# schemat.net
KiCad netlist of a schematic drawn in EAGLE
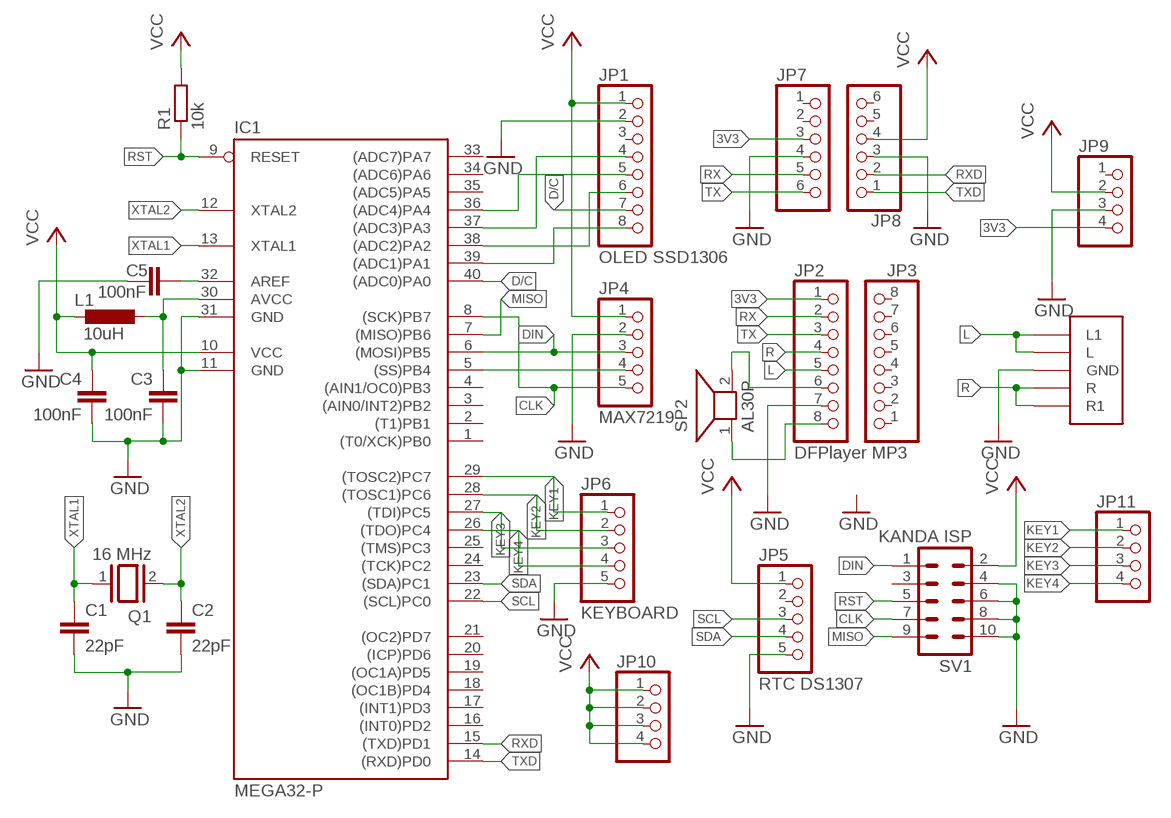
[diagram p0: schematic, sheet 1]

(export (version "E")
  (design (tool "Eeschema 10.0.6"))
  (components
    (comp (ref "C1")
      (value "22pF")
      (footprint "eagle-import:C025-025X050")
      (libsource (lib "eagle-import") (part "C-EU025-025X050"))
    )
    (comp (ref "C2")
      (value "22pF")
      (footprint "eagle-import:C025-025X050")
      (libsource (lib "eagle-import") (part "C-EU025-025X050"))
    )
    (comp (ref "C3")
      (value "100nF")
      (footprint "eagle-import:C025-025X050")
      (libsource (lib "eagle-import") (part "C-EU025-025X050"))
    )
    (comp (ref "C4")
      (value "100nF")
      (footprint "eagle-import:C025-025X050")
      (libsource (lib "eagle-import") (part "C-EU025-025X050"))
    )
    (comp (ref "C5")
      (value "100nF")
      (footprint "eagle-import:C025-025X050")
      (libsource (lib "eagle-import") (part "C-EU025-025X050"))
    )
    (comp (ref "IC1")
      (value "MEGA32-P")
      (footprint "eagle-import:DIL40")
      (fields (field (name "MPN") "ATMEGA16-16PU"))
      (libsource (lib "eagle-import") (part "MEGA16-P"))
    )
    (comp (ref "JP1")
      (value "OLED SSD1306")
      (footprint "eagle-import:1X08")
      (libsource (lib "eagle-import") (part "PINHD-1X8"))
    )
    (comp (ref "JP2")
      (value "DFPlayer MP3")
      (footprint "eagle-import:1X08")
      (libsource (lib "eagle-import") (part "PINHD-1X8"))
    )
    (comp (ref "JP3")
      (value "PINHD-1X8")
      (footprint "eagle-import:1X08")
      (libsource (lib "eagle-import") (part "PINHD-1X8"))
    )
    (comp (ref "JP4")
      (value "MAX7219")
      (footprint "eagle-import:1X05")
      (libsource (lib "eagle-import") (part "PINHD-1X5"))
    )
    (comp (ref "JP5")
      (value "RTC DS1307")
      (footprint "eagle-import:1X05")
      (libsource (lib "eagle-import") (part "PINHD-1X5"))
    )
    (comp (ref "JP6")
      (value "KEYBOARD")
      (footprint "eagle-import:1X05")
      (libsource (lib "eagle-import") (part "PINHD-1X5"))
    )
    (comp (ref "JP7")
      (value "PINHD-1X6")
      (footprint "eagle-import:1X06")
      (libsource (lib "eagle-import") (part "PINHD-1X6"))
    )
    (comp (ref "JP8")
      (value "PINHD-1X6")
      (footprint "eagle-import:1X06")
      (libsource (lib "eagle-import") (part "PINHD-1X6"))
    )
    (comp (ref "JP9")
      (value "PINHD-1X4")
      (footprint "eagle-import:1X04")
      (libsource (lib "eagle-import") (part "PINHD-1X4"))
    )
    (comp (ref "JP10")
      (value "PINHD-1X4")
      (footprint "eagle-import:1X04")
      (libsource (lib "eagle-import") (part "PINHD-1X4"))
    )
    (comp (ref "JP11")
      (value "PINHD-1X4")
      (footprint "eagle-import:1X04")
      (libsource (lib "eagle-import") (part "PINHD-1X4"))
    )
    (comp (ref "L1")
      (value "10uH")
      (footprint "eagle-import:0204_5")
      (libsource (lib "eagle-import") (part "L-EU0204/5"))
    )
    (comp (ref "Q1")
      (value "16 MHz")
      (footprint "eagle-import:QS")
      (libsource (lib "eagle-import") (part "XTAL/S"))
    )
    (comp (ref "R1")
      (value "10k")
      (footprint "eagle-import:0207_7")
      (libsource (lib "eagle-import") (part "R-EU_0207/7"))
    )
    (comp (ref "SP2")
      (value "AL30P")
      (footprint "eagle-import:AL30P")
      (libsource (lib "eagle-import") (part "AL30P"))
    )
    (comp (ref "SV1")
      (value "KANDA ISP")
      (footprint "eagle-import:ML10")
      (libsource (lib "eagle-import") (part "ML10"))
    )
    (comp (ref "U$1")
      (value "STEREO_D")
      (footprint "eagle-import:STEREO_P")
      (libsource (lib "eagle-import") (part "STEREO_D"))
    )
  )
  (nets
    (net (code "1") (name "3V3") (class "Default")
      (node (ref "JP2") (pin "1") (pinfunction "1_1") (pintype "passive"))
      (node (ref "JP7") (pin "3") (pinfunction "3_3") (pintype "passive"))
      (node (ref "JP9") (pin "4") (pinfunction "4_4") (pintype "passive"))
    )
    (net (code "2") (name "CLK") (class "Default")
      (node (ref "IC1") (pin "8") (pinfunction "(SCK)PB7_8") (pintype "bidirectional"))
      (node (ref "JP4") (pin "5") (pinfunction "5_5") (pintype "passive"))
      (node (ref "SV1") (pin "7") (pinfunction "7_7") (pintype "passive"))
    )
    (net (code "3") (name "DIN") (class "Default")
      (node (ref "IC1") (pin "6") (pinfunction "(MOSI)PB5_6") (pintype "bidirectional"))
      (node (ref "JP4") (pin "3") (pinfunction "3_3") (pintype "passive"))
      (node (ref "SV1") (pin "1") (pinfunction "1_1") (pintype "passive"))
    )
    (net (code "4") (name "D{slash}C") (class "Default")
      (node (ref "IC1") (pin "40") (pinfunction "(ADC0)PA0_40") (pintype "bidirectional"))
      (node (ref "JP1") (pin "7") (pinfunction "7_7") (pintype "passive"))
    )
    (net (code "5") (name "GND") (class "Default")
      (node (ref "C1") (pin "2") (pinfunction "2_2") (pintype "passive"))
      (node (ref "C2") (pin "2") (pinfunction "2_2") (pintype "passive"))
      (node (ref "C3") (pin "2") (pinfunction "2_2") (pintype "passive"))
      (node (ref "C4") (pin "2") (pinfunction "2_2") (pintype "passive"))
      (node (ref "C5") (pin "2") (pinfunction "2_2") (pintype "passive"))
      (node (ref "IC1") (pin "11") (pinfunction "GND_11") (pintype "power_in"))
      (node (ref "IC1") (pin "31") (pinfunction "GND_31") (pintype "power_in"))
      (node (ref "JP1") (pin "2") (pinfunction "2_2") (pintype "passive"))
      (node (ref "JP2") (pin "7") (pinfunction "7_7") (pintype "passive"))
      (node (ref "JP4") (pin "2") (pinfunction "2_2") (pintype "passive"))
      (node (ref "JP5") (pin "5") (pinfunction "5_5") (pintype "passive"))
      (node (ref "JP6") (pin "5") (pinfunction "5_5") (pintype "passive"))
      (node (ref "JP7") (pin "4") (pinfunction "4_4") (pintype "passive"))
      (node (ref "JP8") (pin "3") (pinfunction "3_3") (pintype "passive"))
      (node (ref "JP9") (pin "3") (pinfunction "3_3") (pintype "passive"))
      (node (ref "SV1") (pin "10") (pinfunction "10_10") (pintype "passive"))
      (node (ref "SV1") (pin "4") (pinfunction "4_4") (pintype "passive"))
      (node (ref "SV1") (pin "6") (pinfunction "6_6") (pintype "passive"))
      (node (ref "SV1") (pin "8") (pinfunction "8_8") (pintype "passive"))
      (node (ref "U$1") (pin "GND") (pinfunction "GND_GND") (pintype "bidirectional"))
    )
    (net (code "6") (name "KEY1") (class "Default")
      (node (ref "IC1") (pin "29") (pinfunction "(TOSC2)PC7_29") (pintype "bidirectional"))
      (node (ref "JP11") (pin "1") (pinfunction "1_1") (pintype "passive"))
      (node (ref "JP6") (pin "1") (pinfunction "1_1") (pintype "passive"))
    )
    (net (code "7") (name "KEY2") (class "Default")
      (node (ref "IC1") (pin "28") (pinfunction "(TOSC1)PC6_28") (pintype "bidirectional"))
      (node (ref "JP11") (pin "2") (pinfunction "2_2") (pintype "passive"))
      (node (ref "JP6") (pin "2") (pinfunction "2_2") (pintype "passive"))
    )
    (net (code "8") (name "KEY3") (class "Default")
      (node (ref "IC1") (pin "27") (pinfunction "(TDI)PC5_27") (pintype "bidirectional"))
      (node (ref "JP11") (pin "3") (pinfunction "3_3") (pintype "passive"))
      (node (ref "JP6") (pin "3") (pinfunction "3_3") (pintype "passive"))
    )
    (net (code "9") (name "KEY4") (class "Default")
      (node (ref "IC1") (pin "26") (pinfunction "(TDO)PC4_26") (pintype "bidirectional"))
      (node (ref "JP11") (pin "4") (pinfunction "4_4") (pintype "passive"))
      (node (ref "JP6") (pin "4") (pinfunction "4_4") (pintype "passive"))
    )
    (net (code "10") (name "L") (class "Default")
      (node (ref "JP2") (pin "5") (pinfunction "5_5") (pintype "passive"))
      (node (ref "U$1") (pin "L_A") (pinfunction "L1_L_A") (pintype "bidirectional"))
      (node (ref "U$1") (pin "L_B") (pinfunction "L_L_B") (pintype "bidirectional"))
    )
    (net (code "11") (name "MISO") (class "Default")
      (node (ref "IC1") (pin "7") (pinfunction "(MISO)PB6_7") (pintype "bidirectional"))
      (node (ref "SV1") (pin "9") (pinfunction "9_9") (pintype "passive"))
    )
    (net (code "12") (name "Net-(IC1-(ADC1)PA1)") (class "Default")
      (node (ref "IC1") (pin "39") (pinfunction "(ADC1)PA1_39") (pintype "bidirectional"))
      (node (ref "JP1") (pin "8") (pinfunction "8_8") (pintype "passive"))
    )
    (net (code "13") (name "Net-(IC1-(ADC2)PA2)") (class "Default")
      (node (ref "IC1") (pin "38") (pinfunction "(ADC2)PA2_38") (pintype "bidirectional"))
      (node (ref "JP1") (pin "6") (pinfunction "6_6") (pintype "passive"))
    )
    (net (code "14") (name "Net-(IC1-(ADC3)PA3)") (class "Default")
      (node (ref "IC1") (pin "37") (pinfunction "(ADC3)PA3_37") (pintype "bidirectional"))
      (node (ref "JP1") (pin "4") (pinfunction "4_4") (pintype "passive"))
    )
    (net (code "15") (name "Net-(IC1-(ADC4)PA4)") (class "Default")
      (node (ref "IC1") (pin "36") (pinfunction "(ADC4)PA4_36") (pintype "bidirectional"))
      (node (ref "JP1") (pin "5") (pinfunction "5_5") (pintype "passive"))
    )
    (net (code "16") (name "Net-(IC1-(SS)PB4)") (class "Default")
      (node (ref "IC1") (pin "5") (pinfunction "(SS)PB4_5") (pintype "bidirectional"))
      (node (ref "JP4") (pin "4") (pinfunction "4_4") (pintype "passive"))
    )
    (net (code "17") (name "Net-(IC1-AREF)") (class "Default")
      (node (ref "C5") (pin "1") (pinfunction "1_1") (pintype "passive"))
      (node (ref "IC1") (pin "32") (pinfunction "AREF_32") (pintype "passive"))
    )
    (net (code "18") (name "Net-(IC1-AVCC)") (class "Default")
      (node (ref "C3") (pin "1") (pinfunction "1_1") (pintype "passive"))
      (node (ref "IC1") (pin "30") (pinfunction "AVCC_30") (pintype "power_in"))
      (node (ref "L1") (pin "1") (pinfunction "1_1") (pintype "passive"))
    )
    (net (code "19") (name "Net-(JP2-Pad6)") (class "Default")
      (node (ref "JP2") (pin "6") (pinfunction "6_6") (pintype "passive"))
      (node (ref "SP2") (pin "2") (pinfunction "2_2") (pintype "passive"))
    )
    (net (code "20") (name "Net-(JP2-Pad8)") (class "Default")
      (node (ref "JP2") (pin "8") (pinfunction "8_8") (pintype "passive"))
      (node (ref "SP2") (pin "1") (pinfunction "1_1") (pintype "passive"))
    )
    (net (code "21") (name "R") (class "Default")
      (node (ref "JP2") (pin "4") (pinfunction "4_4") (pintype "passive"))
      (node (ref "U$1") (pin "R_A") (pinfunction "R1_R_A") (pintype "bidirectional"))
      (node (ref "U$1") (pin "R_B") (pinfunction "R_R_B") (pintype "bidirectional"))
    )
    (net (code "22") (name "RST") (class "Default")
      (node (ref "IC1") (pin "9") (pinfunction "RESET_9") (pintype "input"))
      (node (ref "R1") (pin "1") (pinfunction "1_1") (pintype "passive"))
      (node (ref "SV1") (pin "5") (pinfunction "5_5") (pintype "passive"))
    )
    (net (code "23") (name "RX") (class "Default")
      (node (ref "JP2") (pin "2") (pinfunction "2_2") (pintype "passive"))
      (node (ref "JP7") (pin "5") (pinfunction "5_5") (pintype "passive"))
    )
    (net (code "24") (name "RXD") (class "Default")
      (node (ref "IC1") (pin "15") (pinfunction "(TXD)PD1_15") (pintype "bidirectional"))
      (node (ref "JP8") (pin "2") (pinfunction "2_2") (pintype "passive"))
    )
    (net (code "25") (name "SCL") (class "Default")
      (node (ref "IC1") (pin "22") (pinfunction "(SCL)PC0_22") (pintype "bidirectional"))
      (node (ref "JP5") (pin "3") (pinfunction "3_3") (pintype "passive"))
    )
    (net (code "26") (name "SDA") (class "Default")
      (node (ref "IC1") (pin "23") (pinfunction "(SDA)PC1_23") (pintype "bidirectional"))
      (node (ref "JP5") (pin "4") (pinfunction "4_4") (pintype "passive"))
    )
    (net (code "27") (name "TX") (class "Default")
      (node (ref "JP2") (pin "3") (pinfunction "3_3") (pintype "passive"))
      (node (ref "JP7") (pin "6") (pinfunction "6_6") (pintype "passive"))
    )
    (net (code "28") (name "TXD") (class "Default")
      (node (ref "IC1") (pin "14") (pinfunction "(RXD)PD0_14") (pintype "bidirectional"))
      (node (ref "JP8") (pin "1") (pinfunction "1_1") (pintype "passive"))
    )
    (net (code "29") (name "VCC") (class "Default")
      (node (ref "C4") (pin "1") (pinfunction "1_1") (pintype "passive"))
      (node (ref "IC1") (pin "10") (pinfunction "VCC_10") (pintype "power_in"))
      (node (ref "JP1") (pin "1") (pinfunction "1_1") (pintype "passive"))
      (node (ref "JP10") (pin "1") (pinfunction "1_1") (pintype "passive"))
      (node (ref "JP10") (pin "2") (pinfunction "2_2") (pintype "passive"))
      (node (ref "JP10") (pin "3") (pinfunction "3_3") (pintype "passive"))
      (node (ref "JP10") (pin "4") (pinfunction "4_4") (pintype "passive"))
      (node (ref "JP4") (pin "1") (pinfunction "1_1") (pintype "passive"))
      (node (ref "JP5") (pin "1") (pinfunction "1_1") (pintype "passive"))
      (node (ref "JP8") (pin "4") (pinfunction "4_4") (pintype "passive"))
      (node (ref "JP9") (pin "2") (pinfunction "2_2") (pintype "passive"))
      (node (ref "L1") (pin "2") (pinfunction "2_2") (pintype "passive"))
      (node (ref "R1") (pin "2") (pinfunction "2_2") (pintype "passive"))
      (node (ref "SV1") (pin "2") (pinfunction "2_2") (pintype "passive"))
    )
    (net (code "30") (name "XTAL1") (class "Default")
      (node (ref "C1") (pin "1") (pinfunction "1_1") (pintype "passive"))
      (node (ref "IC1") (pin "13") (pinfunction "XTAL1_13") (pintype "bidirectional"))
      (node (ref "Q1") (pin "1") (pinfunction "1_1") (pintype "passive"))
    )
    (net (code "31") (name "XTAL2") (class "Default")
      (node (ref "C2") (pin "1") (pinfunction "1_1") (pintype "passive"))
      (node (ref "IC1") (pin "12") (pinfunction "XTAL2_12") (pintype "bidirectional"))
      (node (ref "Q1") (pin "2") (pinfunction "2_2") (pintype "passive"))
    )
    (net (code "32") (name "unconnected-(IC1-(ADC5)PA5-Pad35)") (class "Default")
      (node (ref "IC1") (pin "35") (pinfunction "(ADC5)PA5_35") (pintype "bidirectional"))
    )
    (net (code "33") (name "unconnected-(IC1-(ADC6)PA6-Pad34)") (class "Default")
      (node (ref "IC1") (pin "34") (pinfunction "(ADC6)PA6_34") (pintype "bidirectional"))
    )
    (net (code "34") (name "unconnected-(IC1-(ADC7)PA7-Pad33)") (class "Default")
      (node (ref "IC1") (pin "33") (pinfunction "(ADC7)PA7_33") (pintype "bidirectional"))
    )
    (net (code "35") (name "unconnected-(IC1-(AIN0{slash}INT2)PB2-Pad3)") (class "Default")
      (node (ref "IC1") (pin "3") (pinfunction "(AIN0/INT2)PB2_3") (pintype "bidirectional"))
    )
    (net (code "36") (name "unconnected-(IC1-(AIN1{slash}OC0)PB3-Pad4)") (class "Default")
      (node (ref "IC1") (pin "4") (pinfunction "(AIN1/OC0)PB3_4") (pintype "bidirectional"))
    )
    (net (code "37") (name "unconnected-(IC1-(ICP)PD6-Pad20)") (class "Default")
      (node (ref "IC1") (pin "20") (pinfunction "(ICP)PD6_20") (pintype "bidirectional"))
    )
    (net (code "38") (name "unconnected-(IC1-(INT0)PD2-Pad16)") (class "Default")
      (node (ref "IC1") (pin "16") (pinfunction "(INT0)PD2_16") (pintype "bidirectional"))
    )
    (net (code "39") (name "unconnected-(IC1-(INT1)PD3-Pad17)") (class "Default")
      (node (ref "IC1") (pin "17") (pinfunction "(INT1)PD3_17") (pintype "bidirectional"))
    )
    (net (code "40") (name "unconnected-(IC1-(OC1A)PD5-Pad19)") (class "Default")
      (node (ref "IC1") (pin "19") (pinfunction "(OC1A)PD5_19") (pintype "bidirectional"))
    )
    (net (code "41") (name "unconnected-(IC1-(OC1B)PD4-Pad18)") (class "Default")
      (node (ref "IC1") (pin "18") (pinfunction "(OC1B)PD4_18") (pintype "bidirectional"))
    )
    (net (code "42") (name "unconnected-(IC1-(OC2)PD7-Pad21)") (class "Default")
      (node (ref "IC1") (pin "21") (pinfunction "(OC2)PD7_21") (pintype "bidirectional"))
    )
    (net (code "43") (name "unconnected-(IC1-(T0{slash}XCK)PB0-Pad1)") (class "Default")
      (node (ref "IC1") (pin "1") (pinfunction "(T0/XCK)PB0_1") (pintype "bidirectional"))
    )
    (net (code "44") (name "unconnected-(IC1-(T1)PB1-Pad2)") (class "Default")
      (node (ref "IC1") (pin "2") (pinfunction "(T1)PB1_2") (pintype "bidirectional"))
    )
    (net (code "45") (name "unconnected-(IC1-(TCK)PC2-Pad24)") (class "Default")
      (node (ref "IC1") (pin "24") (pinfunction "(TCK)PC2_24") (pintype "bidirectional"))
    )
    (net (code "46") (name "unconnected-(IC1-(TMS)PC3-Pad25)") (class "Default")
      (node (ref "IC1") (pin "25") (pinfunction "(TMS)PC3_25") (pintype "bidirectional"))
    )
    (net (code "47") (name "unconnected-(JP1-Pad3)") (class "Default")
      (node (ref "JP1") (pin "3") (pinfunction "3_3") (pintype "passive"))
    )
    (net (code "48") (name "unconnected-(JP3-Pad1)") (class "Default")
      (node (ref "JP3") (pin "1") (pinfunction "1_1") (pintype "passive"))
    )
    (net (code "49") (name "unconnected-(JP3-Pad2)") (class "Default")
      (node (ref "JP3") (pin "2") (pinfunction "2_2") (pintype "passive"))
    )
    (net (code "50") (name "unconnected-(JP3-Pad3)") (class "Default")
      (node (ref "JP3") (pin "3") (pinfunction "3_3") (pintype "passive"))
    )
    (net (code "51") (name "unconnected-(JP3-Pad4)") (class "Default")
      (node (ref "JP3") (pin "4") (pinfunction "4_4") (pintype "passive"))
    )
    (net (code "52") (name "unconnected-(JP3-Pad5)") (class "Default")
      (node (ref "JP3") (pin "5") (pinfunction "5_5") (pintype "passive"))
    )
    (net (code "53") (name "unconnected-(JP3-Pad6)") (class "Default")
      (node (ref "JP3") (pin "6") (pinfunction "6_6") (pintype "passive"))
    )
    (net (code "54") (name "unconnected-(JP3-Pad7)") (class "Default")
      (node (ref "JP3") (pin "7") (pinfunction "7_7") (pintype "passive"))
    )
    (net (code "55") (name "unconnected-(JP3-Pad8)") (class "Default")
      (node (ref "JP3") (pin "8") (pinfunction "8_8") (pintype "passive"))
    )
    (net (code "56") (name "unconnected-(JP5-Pad2)") (class "Default")
      (node (ref "JP5") (pin "2") (pinfunction "2_2") (pintype "passive"))
    )
    (net (code "57") (name "unconnected-(JP7-Pad1)") (class "Default")
      (node (ref "JP7") (pin "1") (pinfunction "1_1") (pintype "passive"))
    )
    (net (code "58") (name "unconnected-(JP7-Pad2)") (class "Default")
      (node (ref "JP7") (pin "2") (pinfunction "2_2") (pintype "passive"))
    )
    (net (code "59") (name "unconnected-(JP8-Pad5)") (class "Default")
      (node (ref "JP8") (pin "5") (pinfunction "5_5") (pintype "passive"))
    )
    (net (code "60") (name "unconnected-(JP8-Pad6)") (class "Default")
      (node (ref "JP8") (pin "6") (pinfunction "6_6") (pintype "passive"))
    )
    (net (code "61") (name "unconnected-(JP9-Pad1)") (class "Default")
      (node (ref "JP9") (pin "1") (pinfunction "1_1") (pintype "passive"))
    )
    (net (code "62") (name "unconnected-(SV1-Pad3)") (class "Default")
      (node (ref "SV1") (pin "3") (pinfunction "3_3") (pintype "passive"))
    )
  )
)
